# 1_ADSTM32-Power.net
KiCad netlist of a schematic drawn in Altium Designer
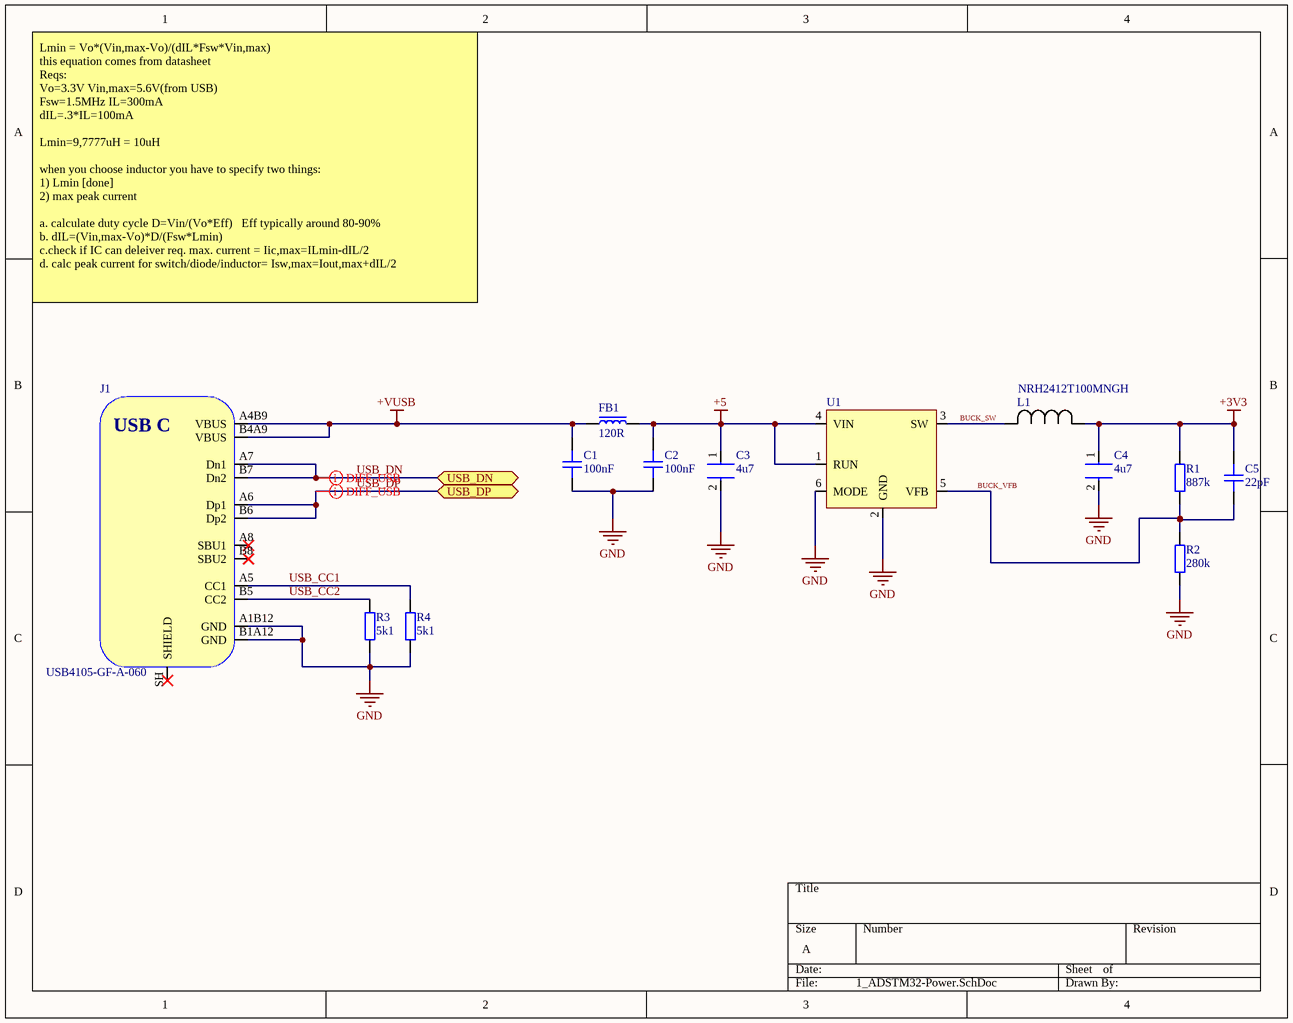
[diagram p0: 1_ADSTM32-Power.SchDoc]

(export (version "E")
  (design (tool "Eeschema 10.0.6"))
  (components
    (comp (ref "C1")
      (value "100nF")
      (footprint "CAP_0603")
      (description "Capacitor SMD 0603")
      (libsource (lib "Schematic-Lib-PhilsLab") (part "CAP_0603"))
    )
    (comp (ref "C2")
      (value "100nF")
      (footprint "CAP_0603")
      (description "Capacitor SMD 0603")
      (libsource (lib "Schematic-Lib-PhilsLab") (part "CAP_0603"))
    )
    (comp (ref "C3")
      (value "4u7")
      (footprint "C2012X7R1C475K125AE")
      (description "Multilayer Ceramic Capacitors MLCC - SMD/SMT 0805 16VDC 4.7uF 10% X7R 1.25mm")
      (fields
        (field (name "MANUFACTURER") "TDK")
        (field (name "MANUFACTURER PART NUMBER") "C2012X7R1C475K125AE")
      )
      (libsource (lib "Schlib1") (part "CAP_0805_16V"))
    )
    (comp (ref "C4")
      (value "4u7")
      (footprint "C2012X7R1C475K125AE")
      (description "Multilayer Ceramic Capacitors MLCC - SMD/SMT 0805 16VDC 4.7uF 10% X7R 1.25mm")
      (fields
        (field (name "MANUFACTURER") "TDK")
        (field (name "MANUFACTURER PART NUMBER") "C2012X7R1C475K125AE")
      )
      (libsource (lib "Schlib1") (part "CAP_0805_16V"))
    )
    (comp (ref "C5")
      (value "22pF")
      (footprint "CAP_0603")
      (description "Capacitor SMD 0603")
      (libsource (lib "Schematic-Lib-PhilsLab") (part "CAP_0603"))
    )
    (comp (ref "FB1")
      (value "120R")
      (footprint "FB_0603")
      (description "Ferrite Bead SMD 0603")
      (libsource (lib "Schematic-Lib-PhilsLab") (part "FB_0603"))
    )
    (comp (ref "J1")
      (value "USB4105-GF-A-060")
      (footprint "USB4105-GF-A-060")
      (description "USB Connector Type C SMT 12 Pin")
      (fields (field (name "MANUFACTURER") "GCT"))
      (libsource (lib "Schematic-Lib-PhilsLab") (part "USB4105-GF-A-060"))
    )
    (comp (ref "L1")
      (value "NRH2412T100MNGH")
      (footprint "NRH2412T100MNGH")
      (description "Power Inductors - SMD 963-LSXNE2424MKT100M RPLCMT PN 2412 10uH 600mOhms")
      (fields (field (name "MANUFACTURER") "TAIYO YUDEN"))
      (libsource (lib "Schlib1") (part "NRH2412T100MNGH"))
    )
    (comp (ref "R1")
      (value "887k")
      (footprint "RES_0603")
      (description "Resistor SMD 0603")
      (libsource (lib "Schematic-Lib-PhilsLab") (part "RES_0603"))
    )
    (comp (ref "R2")
      (value "280k")
      (footprint "RES_0603")
      (description "Resistor SMD 0603")
      (libsource (lib "Schematic-Lib-PhilsLab") (part "RES_0603"))
    )
    (comp (ref "R3")
      (value "5k1")
      (footprint "RES_0603")
      (description "Resistor SMD 0603")
      (libsource (lib "Schematic-Lib-PhilsLab") (part "RES_0603"))
    )
    (comp (ref "R4")
      (value "5k1")
      (footprint "RES_0603")
      (description "Resistor SMD 0603")
      (libsource (lib "Schematic-Lib-PhilsLab") (part "RES_0603"))
    )
    (comp (ref "U1")
      (value "LTC3405ES6#TRMPBF")
      (footprint "SOT-23-6")
      (description "Switching Voltage Regulators 1.5MHz, 300mA Sync Buck Reg in SOT")
      (fields (field (name "MANUFACTURER") "Analog Devices"))
      (libsource (lib "Schlib1") (part "LTC3405ES6#TRMPBF"))
    )
  )
  (nets
    (net (code "1") (name "+3V3") (class "Default")
      (node (ref "C4") (pin "1") (pinfunction "1_1") (pintype "passive"))
      (node (ref "C5") (pin "2") (pinfunction "2_2") (pintype "passive"))
      (node (ref "L1") (pin "1") (pinfunction "1_1") (pintype "passive"))
      (node (ref "R1") (pin "2") (pinfunction "2_2") (pintype "passive"))
    )
    (net (code "2") (name "+5") (class "Default")
      (node (ref "C2") (pin "2") (pinfunction "2_2") (pintype "passive"))
      (node (ref "C3") (pin "1") (pinfunction "1_1") (pintype "passive"))
      (node (ref "FB1") (pin "2") (pinfunction "2_2") (pintype "passive"))
      (node (ref "U1") (pin "1") (pinfunction "RUN_1") (pintype "input"))
      (node (ref "U1") (pin "4") (pinfunction "VIN_4") (pintype "power_in"))
    )
    (net (code "3") (name "+VUSB") (class "Default")
      (node (ref "C1") (pin "2") (pinfunction "2_2") (pintype "passive"))
      (node (ref "FB1") (pin "1") (pinfunction "1_1") (pintype "passive"))
      (node (ref "J1") (pin "A4B9") (pinfunction "VBUS_A4B9") (pintype "passive"))
      (node (ref "J1") (pin "B4A9") (pinfunction "VBUS_B4A9") (pintype "passive"))
    )
    (net (code "4") (name "/BUCK_SW") (class "Default")
      (node (ref "L1") (pin "2") (pinfunction "2_2") (pintype "passive"))
      (node (ref "U1") (pin "3") (pinfunction "SW_3") (pintype "power_in"))
    )
    (net (code "5") (name "/BUCK_VFB") (class "Default")
      (node (ref "C5") (pin "1") (pinfunction "1_1") (pintype "passive"))
      (node (ref "R1") (pin "1") (pinfunction "1_1") (pintype "passive"))
      (node (ref "R2") (pin "2") (pinfunction "2_2") (pintype "passive"))
      (node (ref "U1") (pin "5") (pinfunction "VFB_5") (pintype "input"))
    )
    (net (code "6") (name "/USB_CC1") (class "Default")
      (node (ref "J1") (pin "A5") (pinfunction "CC1_A5") (pintype "passive"))
      (node (ref "R4") (pin "2") (pinfunction "2_2") (pintype "passive"))
    )
    (net (code "7") (name "/USB_CC2") (class "Default")
      (node (ref "J1") (pin "B5") (pinfunction "CC2_B5") (pintype "passive"))
      (node (ref "R3") (pin "2") (pinfunction "2_2") (pintype "passive"))
    )
    (net (code "8") (name "/USB_DN") (class "Default")
      (node (ref "J1") (pin "A7") (pinfunction "Dn1_A7") (pintype "passive"))
      (node (ref "J1") (pin "B7") (pinfunction "Dn2_B7") (pintype "passive"))
    )
    (net (code "9") (name "/USB_DP") (class "Default")
      (node (ref "J1") (pin "A6") (pinfunction "Dp1_A6") (pintype "passive"))
      (node (ref "J1") (pin "B6") (pinfunction "Dp2_B6") (pintype "passive"))
    )
    (net (code "10") (name "GND") (class "Default")
      (node (ref "C1") (pin "1") (pinfunction "1_1") (pintype "passive"))
      (node (ref "C2") (pin "1") (pinfunction "1_1") (pintype "passive"))
      (node (ref "C3") (pin "2") (pinfunction "2_2") (pintype "passive"))
      (node (ref "C4") (pin "2") (pinfunction "2_2") (pintype "passive"))
      (node (ref "J1") (pin "A1B12") (pinfunction "GND_A1B12") (pintype "passive"))
      (node (ref "J1") (pin "B1A12") (pinfunction "GND_B1A12") (pintype "passive"))
      (node (ref "R2") (pin "1") (pinfunction "1_1") (pintype "passive"))
      (node (ref "R3") (pin "1") (pinfunction "1_1") (pintype "passive"))
      (node (ref "R4") (pin "1") (pinfunction "1_1") (pintype "passive"))
      (node (ref "U1") (pin "2") (pinfunction "GND_2") (pintype "power_in"))
      (node (ref "U1") (pin "6") (pinfunction "MODE_6") (pintype "passive"))
    )
    (net (code "11") (name "unconnected-(J1-SBU1-PadA8)") (class "Default")
      (node (ref "J1") (pin "A8") (pinfunction "SBU1_A8") (pintype "passive+no_connect"))
    )
    (net (code "12") (name "unconnected-(J1-SBU2-PadB8)") (class "Default")
      (node (ref "J1") (pin "B8") (pinfunction "SBU2_B8") (pintype "passive+no_connect"))
    )
    (net (code "13") (name "unconnected-(J1-SHIELD-PadSH)") (class "Default")
      (node (ref "J1") (pin "SH") (pinfunction "SHIELD_SH") (pintype "passive+no_connect"))
    )
  )
)
